# Audio.net
KiCad netlist of a schematic drawn in Altium Designer
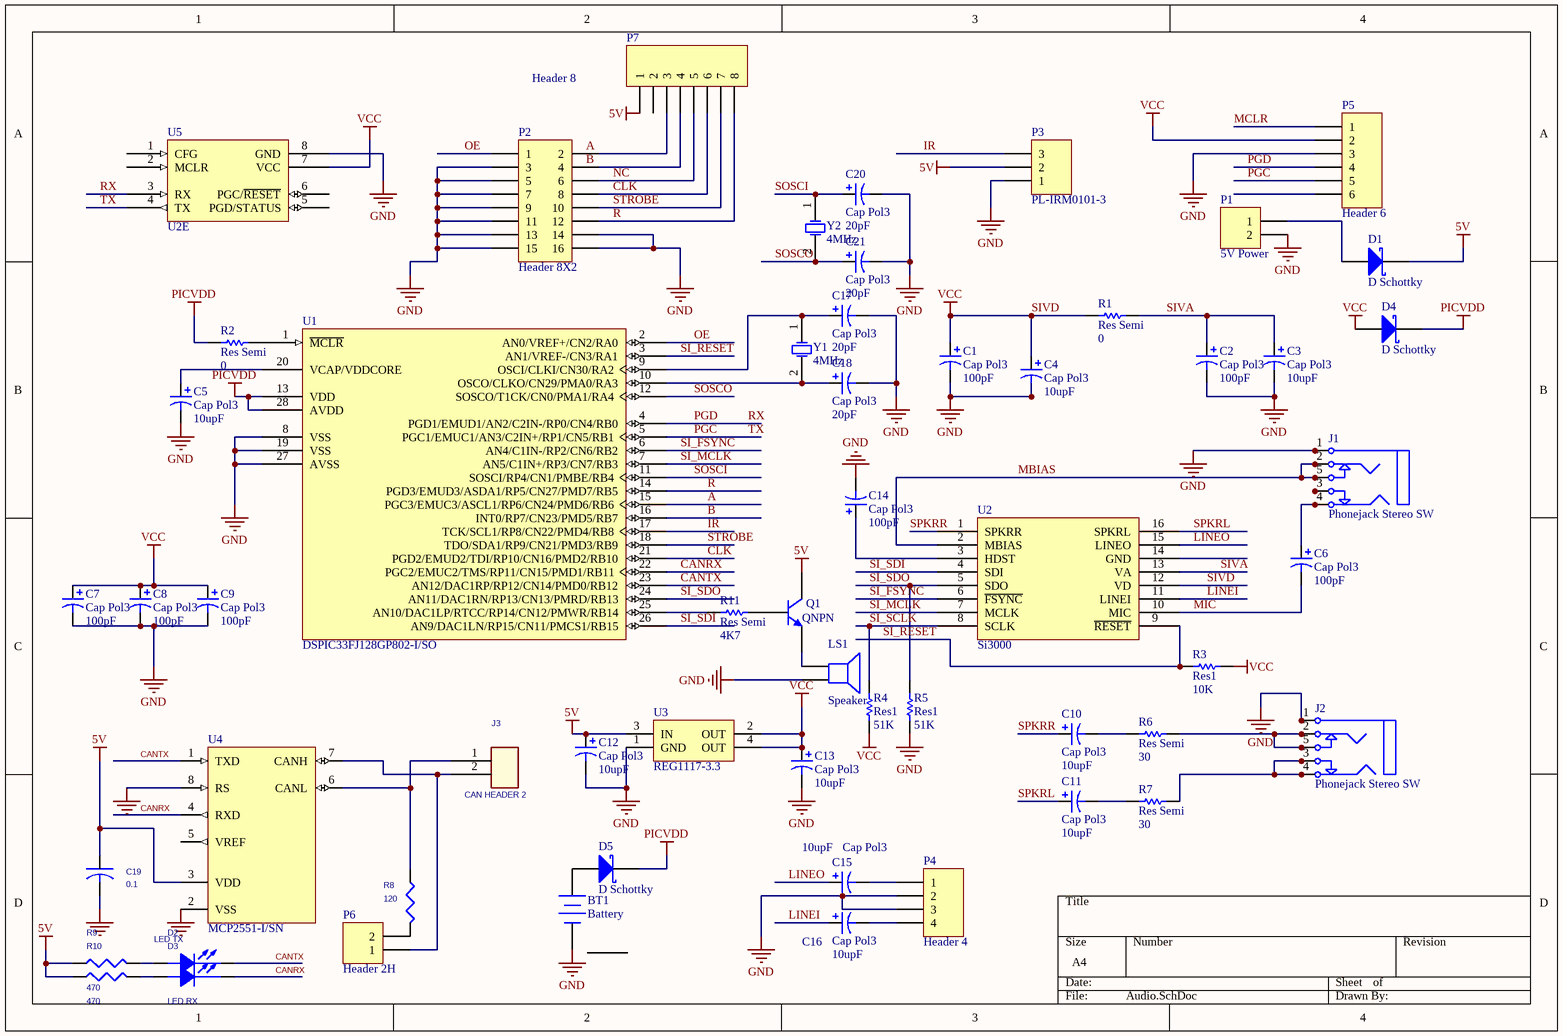
[diagram p0: Audio.SchDoc]

(export (version "E")
  (design (tool "Eeschema 10.0.6"))
  (components
    (comp (ref "BT1")
      (value "Battery")
      (footprint "CR2032")
      (description "Multicell Battery")
      (fields (field (name "PUBLISHER") "Altium Limited"))
      (libsource (lib "Miscellaneous Devices") (part "Battery"))
    )
    (comp (ref "C1")
      (value "Cap Pol3")
      (footprint "CAPC2012L")
      (description "Polarized Capacitor (Surface Mount)")
      (fields (field (name "ALTIUM_VALUE") "100pF") (field (name "PUBLISHER") "Altium Limited"))
      (libsource (lib "Miscellaneous Devices") (part "Cap Pol3"))
    )
    (comp (ref "C2")
      (value "Cap Pol3")
      (footprint "CAPC3225M")
      (description "Polarized Capacitor (Surface Mount)")
      (fields (field (name "ALTIUM_VALUE") "100pF") (field (name "PUBLISHER") "Altium Limited"))
      (libsource (lib "Miscellaneous Devices") (part "Cap Pol3"))
    )
    (comp (ref "C3")
      (value "Cap Pol3")
      (footprint "CAPC2012L")
      (description "Polarized Capacitor (Surface Mount)")
      (fields (field (name "ALTIUM_VALUE") "10upF") (field (name "PUBLISHER") "Altium Limited"))
      (libsource (lib "Miscellaneous Devices") (part "Cap Pol3"))
    )
    (comp (ref "C4")
      (value "Cap Pol3")
      (footprint "CAPC3225M")
      (description "Polarized Capacitor (Surface Mount)")
      (fields (field (name "ALTIUM_VALUE") "10upF") (field (name "PUBLISHER") "Altium Limited"))
      (libsource (lib "Miscellaneous Devices") (part "Cap Pol3"))
    )
    (comp (ref "C5")
      (value "Cap Pol3")
      (footprint "CAPC3225M")
      (description "Polarized Capacitor (Surface Mount)")
      (fields (field (name "ALTIUM_VALUE") "10upF") (field (name "PUBLISHER") "Altium Limited"))
      (libsource (lib "Miscellaneous Devices") (part "Cap Pol3"))
    )
    (comp (ref "C6")
      (value "Cap Pol3")
      (footprint "CAPC2012L")
      (description "Polarized Capacitor (Surface Mount)")
      (fields (field (name "ALTIUM_VALUE") "100pF") (field (name "PUBLISHER") "Altium Limited"))
      (libsource (lib "Miscellaneous Devices") (part "Cap Pol3"))
    )
    (comp (ref "C7")
      (value "Cap Pol3")
      (footprint "CAPC2012L")
      (description "Polarized Capacitor (Surface Mount)")
      (fields (field (name "ALTIUM_VALUE") "100pF") (field (name "PUBLISHER") "Altium Limited"))
      (libsource (lib "Miscellaneous Devices") (part "Cap Pol3"))
    )
    (comp (ref "C8")
      (value "Cap Pol3")
      (footprint "CAPC2012L")
      (description "Polarized Capacitor (Surface Mount)")
      (fields (field (name "ALTIUM_VALUE") "100pF") (field (name "PUBLISHER") "Altium Limited"))
      (libsource (lib "Miscellaneous Devices") (part "Cap Pol3"))
    )
    (comp (ref "C9")
      (value "Cap Pol3")
      (footprint "CAPC2012L")
      (description "Polarized Capacitor (Surface Mount)")
      (fields (field (name "ALTIUM_VALUE") "100pF") (field (name "PUBLISHER") "Altium Limited"))
      (libsource (lib "Miscellaneous Devices") (part "Cap Pol3"))
    )
    (comp (ref "C10")
      (value "Cap Pol3")
      (footprint "CAPC3225M")
      (description "Polarized Capacitor (Surface Mount)")
      (fields (field (name "ALTIUM_VALUE") "10upF") (field (name "PUBLISHER") "Altium Limited"))
      (libsource (lib "Miscellaneous Devices") (part "Cap Pol3"))
    )
    (comp (ref "C11")
      (value "Cap Pol3")
      (footprint "CAPC3225M")
      (description "Polarized Capacitor (Surface Mount)")
      (fields (field (name "ALTIUM_VALUE") "10upF") (field (name "PUBLISHER") "Altium Limited"))
      (libsource (lib "Miscellaneous Devices") (part "Cap Pol3"))
    )
    (comp (ref "C12")
      (value "Cap Pol3")
      (footprint "CAPC3225M")
      (description "Polarized Capacitor (Surface Mount)")
      (fields (field (name "ALTIUM_VALUE") "10upF") (field (name "PUBLISHER") "Altium Limited"))
      (libsource (lib "Miscellaneous Devices") (part "Cap Pol3"))
    )
    (comp (ref "C13")
      (value "Cap Pol3")
      (footprint "CAPC3225M")
      (description "Polarized Capacitor (Surface Mount)")
      (fields (field (name "ALTIUM_VALUE") "10upF") (field (name "PUBLISHER") "Altium Limited"))
      (libsource (lib "Miscellaneous Devices") (part "Cap Pol3"))
    )
    (comp (ref "C14")
      (value "Cap Pol3")
      (footprint "CAPC2012L")
      (description "Polarized Capacitor (Surface Mount)")
      (fields (field (name "ALTIUM_VALUE") "100pF") (field (name "PUBLISHER") "Altium Limited"))
      (libsource (lib "Miscellaneous Devices") (part "Cap Pol3"))
    )
    (comp (ref "C15")
      (value "Cap Pol3")
      (footprint "CAPC3225M")
      (description "Polarized Capacitor (Surface Mount)")
      (fields (field (name "ALTIUM_VALUE") "10upF") (field (name "PUBLISHER") "Altium Limited"))
      (libsource (lib "Miscellaneous Devices") (part "Cap Pol3"))
    )
    (comp (ref "C16")
      (value "Cap Pol3")
      (footprint "CAPC3225M")
      (description "Polarized Capacitor (Surface Mount)")
      (fields (field (name "ALTIUM_VALUE") "10upF") (field (name "PUBLISHER") "Altium Limited"))
      (libsource (lib "Miscellaneous Devices") (part "Cap Pol3"))
    )
    (comp (ref "C17")
      (value "Cap Pol3")
      (footprint "CAPC2012L")
      (description "Polarized Capacitor (Surface Mount)")
      (fields (field (name "ALTIUM_VALUE") "20pF") (field (name "PUBLISHER") "Altium Limited"))
      (libsource (lib "Miscellaneous Devices") (part "Cap Pol3"))
    )
    (comp (ref "C18")
      (value "Cap Pol3")
      (footprint "CAPC2012L")
      (description "Polarized Capacitor (Surface Mount)")
      (fields (field (name "ALTIUM_VALUE") "20pF") (field (name "PUBLISHER") "Altium Limited"))
      (libsource (lib "Miscellaneous Devices") (part "Cap Pol3"))
    )
    (comp (ref "C19") (value "0.1") (footprint "CAPC2012L") (libsource (lib "*") (part "C_Dup1")))
    (comp (ref "C20")
      (value "Cap Pol3")
      (footprint "CAPC2012L")
      (description "Polarized Capacitor (Surface Mount)")
      (fields (field (name "ALTIUM_VALUE") "20pF") (field (name "PUBLISHER") "Altium Limited"))
      (libsource (lib "Miscellaneous Devices") (part "Cap Pol3"))
    )
    (comp (ref "C21")
      (value "Cap Pol3")
      (footprint "CAPC2012L")
      (description "Polarized Capacitor (Surface Mount)")
      (fields (field (name "ALTIUM_VALUE") "20pF") (field (name "PUBLISHER") "Altium Limited"))
      (libsource (lib "Miscellaneous Devices") (part "Cap Pol3"))
    )
    (comp (ref "D1")
      (value "D Schottky")
      (footprint "DIO10.46-5.3x2.8")
      (description "Schottky Diode")
      (fields (field (name "PUBLISHER") "Altium Limited"))
      (libsource (lib "Miscellaneous Devices") (part "D Schottky"))
    )
    (comp (ref "D2") (value "LED TX") (footprint "DSO-F2/D6.1") (libsource (lib "*") (part "LED")))
    (comp (ref "D3") (value "LED RX") (footprint "DSO-F2/D6.1") (libsource (lib "*") (part "LED")))
    (comp (ref "D4")
      (value "D Schottky")
      (footprint "DIO10.46-5.3x2.8")
      (description "Schottky Diode")
      (fields (field (name "PUBLISHER") "Altium Limited"))
      (libsource (lib "Miscellaneous Devices") (part "D Schottky"))
    )
    (comp (ref "D5")
      (value "D Schottky")
      (footprint "DIO10.46-5.3x2.8")
      (description "Schottky Diode")
      (fields (field (name "PUBLISHER") "Altium Limited"))
      (libsource (lib "Miscellaneous Devices") (part "D Schottky"))
    )
    (comp (ref "J1")
      (value "Phonejack Stereo SW")
      (footprint "AUDIO-JACK")
      (description "3-Conductor Jack with 2 break contacts (normals) and 2 auxiliary make contacts")
      (fields (field (name "PUBLISHER") "Altium Limited"))
      (libsource (lib "Miscellaneous Connectors") (part "Phonejack Stereo SW"))
    )
    (comp (ref "J2")
      (value "Phonejack Stereo SW")
      (footprint "AUDIO-JACK")
      (description "3-Conductor Jack with 2 break contacts (normals) and 2 auxiliary make contacts")
      (fields (field (name "PUBLISHER") "Altium Limited"))
      (libsource (lib "Miscellaneous Connectors") (part "Phonejack Stereo SW"))
    )
    (comp (ref "J3")
      (value "CAN HEADER 2")
      (footprint "DOMINO SMALL 2 PIN_REV2")
      (libsource (lib "*") (part "CON2"))
    )
    (comp (ref "LS1")
      (value "Speaker")
      (footprint "PIN2")
      (description "Loudspeaker")
      (fields (field (name "PUBLISHER") "Altium Limited"))
      (libsource (lib "Miscellaneous Devices") (part "Speaker"))
    )
    (comp (ref "P1")
      (value "5V Power")
      (footprint "DOMINO SMALL 2 PIN_REV2")
      (description "Header, 2-Pin")
      (fields (field (name "PUBLISHER") "Altium Limited"))
      (libsource (lib "Miscellaneous Connectors") (part "Header 2"))
    )
    (comp (ref "P2")
      (value "Header 8X2")
      (footprint "HDR2X8")
      (description "Header, 8-Pin, Dual row")
      (fields (field (name "PUBLISHER") "Altium Limited"))
      (libsource (lib "Miscellaneous Connectors") (part "Header 8X2"))
    )
    (comp (ref "P3")
      (value "PL-IRM0101-3")
      (footprint "HDR1X3")
      (description "Header, 3-Pin")
      (fields (field (name "PUBLISHER") "Altium Limited"))
      (libsource (lib "Miscellaneous Connectors") (part "Header 3"))
    )
    (comp (ref "P4")
      (value "Header 4")
      (footprint "HDR1X4")
      (description "Header, 4-Pin")
      (fields (field (name "PUBLISHER") "Altium Limited"))
      (libsource (lib "Miscellaneous Connectors") (part "Header 4"))
    )
    (comp (ref "P5")
      (value "Header 6")
      (footprint "HDR1X6")
      (description "Header, 6-Pin")
      (fields (field (name "PUBLISHER") "Altium Limited"))
      (libsource (lib "Miscellaneous Connectors") (part "Header 6"))
    )
    (comp (ref "P6")
      (value "Header 2H")
      (footprint "RESC2012M")
      (description "Header, 2-Pin, Right Angle")
      (fields (field (name "PUBLISHER") "Altium Limited"))
      (libsource (lib "Miscellaneous Connectors") (part "Header 2H"))
    )
    (comp (ref "P7")
      (value "Header 8")
      (footprint "HDR1X8")
      (description "Header, 8-Pin")
      (fields (field (name "PUBLISHER") "Altium Limited"))
      (libsource (lib "Miscellaneous Connectors") (part "Header 8"))
    )
    (comp (ref "Q1")
      (value "QNPN")
      (footprint "SOT95P240-3M")
      (description "NPN Bipolar Transistor")
      (fields (field (name "PUBLISHER") "Altium Limited"))
      (libsource (lib "Miscellaneous Devices") (part "QNPN"))
    )
    (comp (ref "R1")
      (value "Res Semi")
      (footprint "RESC2012L")
      (description "Semiconductor Resistor")
      (fields (field (name "ALTIUM_VALUE") "0") (field (name "PUBLISHER") "Altium Limited"))
      (libsource (lib "Miscellaneous Devices") (part "Res Semi"))
    )
    (comp (ref "R2")
      (value "Res Semi")
      (footprint "RESC2012L")
      (description "Semiconductor Resistor")
      (fields (field (name "ALTIUM_VALUE") "0") (field (name "PUBLISHER") "Altium Limited"))
      (libsource (lib "Miscellaneous Devices") (part "Res Semi"))
    )
    (comp (ref "R3")
      (value "Res1")
      (footprint "RESC2012M")
      (description "Resistor")
      (fields (field (name "ALTIUM_VALUE") "10K") (field (name "PUBLISHER") "Altium Limited"))
      (libsource (lib "Miscellaneous Devices") (part "Res1"))
    )
    (comp (ref "R4")
      (value "Res1")
      (footprint "RESC2012M")
      (description "Resistor")
      (fields (field (name "ALTIUM_VALUE") "51K") (field (name "PUBLISHER") "Altium Limited"))
      (libsource (lib "Miscellaneous Devices") (part "Res1"))
    )
    (comp (ref "R5")
      (value "Res1")
      (footprint "RESC2012M")
      (description "Resistor")
      (fields (field (name "ALTIUM_VALUE") "51K") (field (name "PUBLISHER") "Altium Limited"))
      (libsource (lib "Miscellaneous Devices") (part "Res1"))
    )
    (comp (ref "R6")
      (value "Res Semi")
      (footprint "RESC2012L")
      (description "Semiconductor Resistor")
      (fields (field (name "ALTIUM_VALUE") "30") (field (name "PUBLISHER") "Altium Limited"))
      (libsource (lib "Miscellaneous Devices") (part "Res Semi"))
    )
    (comp (ref "R7")
      (value "Res Semi")
      (footprint "RESC2012L")
      (description "Semiconductor Resistor")
      (fields (field (name "ALTIUM_VALUE") "30") (field (name "PUBLISHER") "Altium Limited"))
      (libsource (lib "Miscellaneous Devices") (part "Res Semi"))
    )
    (comp (ref "R8") (value "120") (footprint "RESC2012M") (libsource (lib "*") (part "R_Dup1")))
    (comp (ref "R9") (value "470") (footprint "RESC2012M") (libsource (lib "*") (part "R_Dup1")))
    (comp (ref "R10") (value "470") (footprint "RESC2012M") (libsource (lib "*") (part "R_Dup1")))
    (comp (ref "R11")
      (value "Res Semi")
      (footprint "RESC2012L")
      (description "Semiconductor Resistor")
      (fields (field (name "ALTIUM_VALUE") "4K7") (field (name "PUBLISHER") "Altium Limited"))
      (libsource (lib "Miscellaneous Devices") (part "Res Semi"))
    )
    (comp (ref "U1")
      (value "DSPIC33FJ128GP802-I/SO")
      (footprint "SOIC-SO28_N")
      (fields (field (name "PUBLISHER") "Altium Limited"))
      (libsource (lib "Microchip DSC 16-Bit dsPIC33F") (part "DSPIC33FJ128GP802-I/SO"))
    )
    (comp (ref "U2")
      (value "Si3000")
      (footprint "SOIC127P1041-16M")
      (libsource (lib "AudioLib") (part "Si3000"))
    )
    (comp (ref "U3")
      (value "REG1117-3.3")
      (footprint "ZZ311")
      (description "800mA and 1A Low Dropout Positive Regulator 2.85V, 3.3V, 5V, and Adjustable")
      (fields (field (name "PUBLISHER") "Altium Limited"))
      (libsource (lib "BB Power Mgt Voltage Regulator") (part "REG1117-3.3"))
    )
    (comp (ref "U4")
      (value "MCP2551-I/SN")
      (footprint "SOIC-SN8_N")
      (description "High-Speed CAN Transceiver, 8-Pin SOIC, Industrial Temperature")
      (fields (field (name "PUBLISHER") "Altium Limited"))
      (libsource (lib "Microchip Interface") (part "MCP2551-I/SN"))
    )
    (comp (ref "U5") (value "U2E") (footprint "U2E") (libsource (lib "CUTL") (part "U2E")))
    (comp (ref "Y1")
      (value "4MHz")
      (footprint "BCY-W2/E4.7")
      (description "Crystal Oscillator")
      (fields (field (name "PUBLISHER") "Altium Limited"))
      (libsource (lib "Miscellaneous Devices") (part "XTAL"))
    )
    (comp (ref "Y2")
      (value "4MHz")
      (footprint "BCY-W2/D2.1")
      (description "Crystal Oscillator")
      (fields (field (name "PUBLISHER") "Altium Limited"))
      (libsource (lib "Miscellaneous Devices") (part "XTAL"))
    )
  )
  (nets
    (net (code "1") (name "/A") (class "Default")
      (node (ref "U1") (pin "15") (pinfunction "PGC3/EMUC3/ASCL1/RP6/CN24/PMD6/RB6_15") (pintype "bidirectional"))
    )
    (net (code "2") (name "/B") (class "Default")
      (node (ref "U1") (pin "16") (pinfunction "INT0/RP7/CN23/PMD5/RB7_16") (pintype "bidirectional"))
    )
    (net (code "3") (name "/CANRX") (class "Default")
      (node (ref "D3") (pin "2") (pinfunction "CATHODE_2") (pintype "passive"))
      (node (ref "U1") (pin "22") (pinfunction "PGC2/EMUC2/TMS/RP11/CN15/PMD1/RB11_22") (pintype "bidirectional"))
      (node (ref "U4") (pin "4") (pinfunction "RXD_4") (pintype "output"))
    )
    (net (code "4") (name "/CANTX") (class "Default")
      (node (ref "D2") (pin "2") (pinfunction "CATHODE_2") (pintype "passive"))
      (node (ref "U1") (pin "23") (pinfunction "AN12/DAC1RP/RP12/CN14/PMD0/RB12_23") (pintype "bidirectional"))
      (node (ref "U4") (pin "1") (pinfunction "TXD_1") (pintype "input"))
    )
    (net (code "5") (name "/CLK") (class "Default")
      (node (ref "P2") (pin "8") (pinfunction "8_8") (pintype "passive"))
      (node (ref "P7") (pin "6") (pinfunction "6_6") (pintype "passive"))
      (node (ref "U1") (pin "21") (pinfunction "PGD2/EMUD2/TDI/RP10/CN16/PMD2/RB10_21") (pintype "bidirectional"))
    )
    (net (code "6") (name "/IR") (class "Default")
      (node (ref "P3") (pin "3") (pinfunction "3_3") (pintype "passive"))
      (node (ref "U1") (pin "17") (pinfunction "TCK/SCL1/RP8/CN22/PMD4/RB8_17") (pintype "bidirectional"))
    )
    (net (code "7") (name "/LINEI") (class "Default")
      (node (ref "C16") (pin "1") (pinfunction "1_1") (pintype "passive"))
      (node (ref "U2") (pin "11") (pinfunction "LINEI_11") (pintype "passive"))
    )
    (net (code "8") (name "/LINEO") (class "Default")
      (node (ref "C15") (pin "1") (pinfunction "1_1") (pintype "passive"))
      (node (ref "U2") (pin "15") (pinfunction "LINEO_15") (pintype "passive"))
    )
    (net (code "9") (name "/MBIAS") (class "Default")
      (node (ref "J1") (pin "2") (pinfunction "2_2") (pintype "passive"))
      (node (ref "J1") (pin "2A") (pinfunction "2A_2A") (pintype "passive"))
      (node (ref "J1") (pin "2B") (pinfunction "2B_2B") (pintype "passive"))
      (node (ref "J1") (pin "5") (pinfunction "5_5") (pintype "passive"))
      (node (ref "J1") (pin "5A") (pinfunction "5A_5A") (pintype "passive"))
      (node (ref "J1") (pin "5B") (pinfunction "5B_5B") (pintype "passive"))
      (node (ref "U2") (pin "2") (pinfunction "MBIAS_2") (pintype "passive"))
    )
    (net (code "10") (name "/MCLR") (class "Default")
      (node (ref "P5") (pin "1") (pinfunction "1_1") (pintype "passive"))
    )
    (net (code "11") (name "/MIC") (class "Default")
      (node (ref "C6") (pin "2") (pinfunction "2_2") (pintype "passive"))
      (node (ref "U2") (pin "10") (pinfunction "MIC_10") (pintype "passive"))
    )
    (net (code "12") (name "/NC") (class "Default")
      (node (ref "P2") (pin "6") (pinfunction "6_6") (pintype "passive"))
      (node (ref "P7") (pin "5") (pinfunction "5_5") (pintype "passive"))
    )
    (net (code "13") (name "/OE") (class "Default")
      (node (ref "P2") (pin "1") (pinfunction "1_1") (pintype "passive"))
      (node (ref "U1") (pin "2") (pinfunction "AN0/VREF+/CN2/RA0_2") (pintype "bidirectional"))
    )
    (net (code "14") (name "/PGC") (class "Default")
      (node (ref "P5") (pin "5") (pinfunction "5_5") (pintype "passive"))
      (node (ref "U1") (pin "5") (pinfunction "PGC1/EMUC1/AN3/C2IN+/RP1/CN5/RB1_5") (pintype "bidirectional"))
      (node (ref "U5") (pin "4") (pinfunction "TX_4") (pintype "output"))
    )
    (net (code "15") (name "/PGD") (class "Default")
      (node (ref "P5") (pin "4") (pinfunction "4_4") (pintype "passive"))
      (node (ref "U1") (pin "4") (pinfunction "PGD1/EMUD1/AN2/C2IN-/RP0/CN4/RB0_4") (pintype "bidirectional"))
      (node (ref "U5") (pin "3") (pinfunction "RX_3") (pintype "input"))
    )
    (net (code "16") (name "/R") (class "Default")
      (node (ref "P2") (pin "12") (pinfunction "12_12") (pintype "passive"))
      (node (ref "P7") (pin "8") (pinfunction "8_8") (pintype "passive"))
      (node (ref "U1") (pin "14") (pinfunction "PGD3/EMUD3/ASDA1/RP5/CN27/PMD7/RB5_14") (pintype "bidirectional"))
    )
    (net (code "17") (name "/SIVA") (class "Default")
      (node (ref "C2") (pin "1") (pinfunction "1_1") (pintype "passive"))
      (node (ref "C3") (pin "1") (pinfunction "1_1") (pintype "passive"))
      (node (ref "R1") (pin "2") (pinfunction "2_2") (pintype "passive"))
      (node (ref "U2") (pin "13") (pinfunction "VA_13") (pintype "passive"))
    )
    (net (code "18") (name "/SI_FSYNC") (class "Default")
      (node (ref "U1") (pin "6") (pinfunction "AN4/C1IN-/RP2/CN6/RB2_6") (pintype "bidirectional"))
      (node (ref "U2") (pin "6") (pinfunction "~{FSYNC}_6") (pintype "passive"))
    )
    (net (code "19") (name "/SI_MCLK") (class "Default")
      (node (ref "U1") (pin "7") (pinfunction "AN5/C1IN+/RP3/CN7/RB3_7") (pintype "bidirectional"))
      (node (ref "U2") (pin "7") (pinfunction "MCLK_7") (pintype "passive"))
    )
    (net (code "20") (name "/SI_RESET") (class "Default")
      (node (ref "R3") (pin "2") (pinfunction "2_2") (pintype "passive"))
      (node (ref "U1") (pin "3") (pinfunction "AN1/VREF-/CN3/RA1_3") (pintype "bidirectional"))
      (node (ref "U2") (pin "9") (pinfunction "~{RESET}_9") (pintype "passive"))
    )
    (net (code "21") (name "/SI_SCLK") (class "Default")
      (node (ref "R4") (pin "2") (pinfunction "2_2") (pintype "passive"))
      (node (ref "U2") (pin "8") (pinfunction "SCLK_8") (pintype "passive"))
    )
    (net (code "22") (name "/SI_SDI") (class "Default")
      (node (ref "U1") (pin "26") (pinfunction "AN9/DAC1LN/RP15/CN11/PMCS1/RB15_26") (pintype "bidirectional"))
      (node (ref "U2") (pin "4") (pinfunction "SDI_4") (pintype "passive"))
    )
    (net (code "23") (name "/SI_SDO") (class "Default")
      (node (ref "R5") (pin "2") (pinfunction "2_2") (pintype "passive"))
      (node (ref "U1") (pin "24") (pinfunction "AN11/DAC1RN/RP13/CN13/PMRD/RB13_24") (pintype "bidirectional"))
      (node (ref "U2") (pin "5") (pinfunction "SDO_5") (pintype "passive"))
    )
    (net (code "24") (name "/SOSCI") (class "Default")
      (node (ref "C20") (pin "1") (pinfunction "1_1") (pintype "passive"))
      (node (ref "U1") (pin "11") (pinfunction "SOSCI/RP4/CN1/PMBE/RB4_11") (pintype "bidirectional"))
      (node (ref "Y2") (pin "1") (pinfunction "OSC1_1") (pintype "passive"))
    )
    (net (code "25") (name "/SOSCO") (class "Default")
      (node (ref "C21") (pin "1") (pinfunction "1_1") (pintype "passive"))
      (node (ref "U1") (pin "12") (pinfunction "SOSCO/T1CK/CN0/PMA1/RA4_12") (pintype "bidirectional"))
      (node (ref "Y2") (pin "2") (pinfunction "OSC2_2") (pintype "passive"))
    )
    (net (code "26") (name "/SPKRL") (class "Default")
      (node (ref "C11") (pin "1") (pinfunction "1_1") (pintype "passive"))
      (node (ref "U2") (pin "16") (pinfunction "SPKRL_16") (pintype "passive"))
    )
    (net (code "27") (name "/SPKRR") (class "Default")
      (node (ref "C10") (pin "1") (pinfunction "1_1") (pintype "passive"))
      (node (ref "U2") (pin "1") (pinfunction "SPKRR_1") (pintype "passive"))
    )
    (net (code "28") (name "/STROBE") (class "Default")
      (node (ref "P2") (pin "10") (pinfunction "10_10") (pintype "passive"))
      (node (ref "P7") (pin "7") (pinfunction "7_7") (pintype "passive"))
      (node (ref "U1") (pin "18") (pinfunction "TDO/SDA1/RP9/CN21/PMD3/RB9_18") (pintype "bidirectional"))
    )
    (net (code "29") (name "5V") (class "Default")
      (node (ref "C12") (pin "1") (pinfunction "1_1") (pintype "passive"))
      (node (ref "C19") (pin "1") (pinfunction "1_1") (pintype "passive"))
      (node (ref "D1") (pin "2") (pinfunction "K_2") (pintype "passive"))
      (node (ref "P3") (pin "2") (pinfunction "2_2") (pintype "passive"))
      (node (ref "P7") (pin "1") (pinfunction "1_1") (pintype "passive"))
      (node (ref "Q1") (pin "3") (pinfunction "C_3") (pintype "passive"))
      (node (ref "R10") (pin "1") (pinfunction "1_1") (pintype "passive"))
      (node (ref "R9") (pin "1") (pinfunction "1_1") (pintype "passive"))
      (node (ref "U3") (pin "3") (pinfunction "IN_3") (pintype "power_in"))
      (node (ref "U4") (pin "3") (pinfunction "VDD_3") (pintype "power_in"))
    )
    (net (code "30") (name "GND") (class "Default")
      (node (ref "BT1") (pin "1") (pinfunction "-_1") (pintype "passive"))
      (node (ref "C1") (pin "2") (pinfunction "2_2") (pintype "passive"))
      (node (ref "C12") (pin "2") (pinfunction "2_2") (pintype "passive"))
      (node (ref "C13") (pin "2") (pinfunction "2_2") (pintype "passive"))
      (node (ref "C14") (pin "2") (pinfunction "2_2") (pintype "passive"))
      (node (ref "C17") (pin "2") (pinfunction "2_2") (pintype "passive"))
      (node (ref "C18") (pin "2") (pinfunction "2_2") (pintype "passive"))
      (node (ref "C19") (pin "2") (pinfunction "2_2") (pintype "passive"))
      (node (ref "C2") (pin "2") (pinfunction "2_2") (pintype "passive"))
      (node (ref "C20") (pin "2") (pinfunction "2_2") (pintype "passive"))
      (node (ref "C21") (pin "2") (pinfunction "2_2") (pintype "passive"))
      (node (ref "C3") (pin "2") (pinfunction "2_2") (pintype "passive"))
      (node (ref "C4") (pin "2") (pinfunction "2_2") (pintype "passive"))
      (node (ref "C5") (pin "2") (pinfunction "2_2") (pintype "passive"))
      (node (ref "C7") (pin "2") (pinfunction "2_2") (pintype "passive"))
      (node (ref "C8") (pin "2") (pinfunction "2_2") (pintype "passive"))
      (node (ref "C9") (pin "2") (pinfunction "2_2") (pintype "passive"))
      (node (ref "J1") (pin "1") (pinfunction "1_1") (pintype "passive"))
      (node (ref "J1") (pin "1A") (pinfunction "1A_1A") (pintype "passive"))
      (node (ref "J1") (pin "1B") (pinfunction "1B_1B") (pintype "passive"))
      (node (ref "J2") (pin "1") (pinfunction "1_1") (pintype "passive"))
      (node (ref "J2") (pin "1A") (pinfunction "1A_1A") (pintype "passive"))
      (node (ref "J2") (pin "1B") (pinfunction "1B_1B") (pintype "passive"))
      (node (ref "LS1") (pin "2") (pinfunction "2_2") (pintype "passive"))
      (node (ref "P1") (pin "2") (pinfunction "2_2") (pintype "passive"))
      (node (ref "P2") (pin "11") (pinfunction "11_11") (pintype "passive"))
      (node (ref "P2") (pin "13") (pinfunction "13_13") (pintype "passive"))
      (node (ref "P2") (pin "14") (pinfunction "14_14") (pintype "passive"))
      (node (ref "P2") (pin "15") (pinfunction "15_15") (pintype "passive"))
      (node (ref "P2") (pin "16") (pinfunction "16_16") (pintype "passive"))
      (node (ref "P2") (pin "3") (pinfunction "3_3") (pintype "passive"))
      (node (ref "P2") (pin "5") (pinfunction "5_5") (pintype "passive"))
      (node (ref "P2") (pin "7") (pinfunction "7_7") (pintype "passive"))
      (node (ref "P2") (pin "9") (pinfunction "9_9") (pintype "passive"))
      (node (ref "P3") (pin "1") (pinfunction "1_1") (pintype "passive"))
      (node (ref "P4") (pin "2") (pinfunction "2_2") (pintype "passive"))
      (node (ref "P4") (pin "3") (pinfunction "3_3") (pintype "passive"))
      (node (ref "P5") (pin "3") (pinfunction "3_3") (pintype "passive"))
      (node (ref "R5") (pin "1") (pinfunction "1_1") (pintype "passive"))
      (node (ref "U1") (pin "19") (pinfunction "VSS_19") (pintype "power_in"))
      (node (ref "U1") (pin "27") (pinfunction "AVSS_27") (pintype "power_in"))
      (node (ref "U1") (pin "8") (pinfunction "VSS_8") (pintype "power_in"))
      (node (ref "U3") (pin "1") (pinfunction "GND_1") (pintype "power_in"))
      (node (ref "U4") (pin "2") (pinfunction "VSS_2") (pintype "power_in"))
      (node (ref "U4") (pin "8") (pinfunction "RS_8") (pintype "input"))
      (node (ref "U5") (pin "8") (pinfunction "GND_8") (pintype "power_in"))
    )
    (net (code "31") (name "Net-(C6-Pad1)") (class "Default")
      (node (ref "C6") (pin "1") (pinfunction "1_1") (pintype "passive"))
      (node (ref "J1") (pin "4") (pinfunction "4_4") (pintype "passive"))
      (node (ref "J1") (pin "4A") (pinfunction "4A_4A") (pintype "passive"))
      (node (ref "J1") (pin "4B") (pinfunction "4B_4B") (pintype "passive"))
    )
    (net (code "32") (name "Net-(C10-Pad2)") (class "Default")
      (node (ref "C10") (pin "2") (pinfunction "2_2") (pintype "passive"))
      (node (ref "R6") (pin "1") (pinfunction "1_1") (pintype "passive"))
    )
    (net (code "33") (name "Net-(C11-Pad2)") (class "Default")
      (node (ref "C11") (pin "2") (pinfunction "2_2") (pintype "passive"))
      (node (ref "R7") (pin "1") (pinfunction "1_1") (pintype "passive"))
    )
    (net (code "34") (name "Net-(C15-Pad2)") (class "Default")
      (node (ref "C15") (pin "2") (pinfunction "2_2") (pintype "passive"))
      (node (ref "P4") (pin "1") (pinfunction "1_1") (pintype "passive"))
    )
    (net (code "35") (name "Net-(C16-Pad2)") (class "Default")
      (node (ref "C16") (pin "2") (pinfunction "2_2") (pintype "passive"))
      (node (ref "P4") (pin "4") (pinfunction "4_4") (pintype "passive"))
    )
    (net (code "36") (name "Net-(D1-A)") (class "Default")
      (node (ref "D1") (pin "1") (pinfunction "A_1") (pintype "passive"))
      (node (ref "P1") (pin "1") (pinfunction "1_1") (pintype "passive"))
    )
    (net (code "37") (name "Net-(D2-ANODE)") (class "Default")
      (node (ref "D2") (pin "1") (pinfunction "ANODE_1") (pintype "passive"))
      (node (ref "R9") (pin "2") (pinfunction "2_2") (pintype "passive"))
    )
    (net (code "38") (name "Net-(D3-ANODE)") (class "Default")
      (node (ref "D3") (pin "1") (pinfunction "ANODE_1") (pintype "passive"))
      (node (ref "R10") (pin "2") (pinfunction "2_2") (pintype "passive"))
    )
    (net (code "39") (name "Net-(D5-A)") (class "Default")
      (node (ref "BT1") (pin "2") (pinfunction "+_2") (pintype "passive"))
      (node (ref "D5") (pin "1") (pinfunction "A_1") (pintype "passive"))
    )
    (net (code "40") (name "Net-(J1-Pad3)") (class "Default")
      (node (ref "J1") (pin "3") (pinfunction "3_3") (pintype "passive"))
      (node (ref "J1") (pin "3A") (pinfunction "3A_3A") (pintype "passive"))
      (node (ref "J1") (pin "3B") (pinfunction "3B_3B") (pintype "passive"))
    )
    (net (code "41") (name "Net-(J2-Pad2)") (class "Default")
      (node (ref "J2") (pin "2") (pinfunction "2_2") (pintype "passive"))
      (node (ref "J2") (pin "2A") (pinfunction "2A_2A") (pintype "passive"))
      (node (ref "J2") (pin "2B") (pinfunction "2B_2B") (pintype "passive"))
      (node (ref "J2") (pin "5") (pinfunction "5_5") (pintype "passive"))
      (node (ref "J2") (pin "5A") (pinfunction "5A_5A") (pintype "passive"))
      (node (ref "J2") (pin "5B") (pinfunction "5B_5B") (pintype "passive"))
      (node (ref "R6") (pin "2") (pinfunction "2_2") (pintype "passive"))
    )
    (net (code "42") (name "Net-(J2-Pad3)") (class "Default")
      (node (ref "J2") (pin "3") (pinfunction "3_3") (pintype "passive"))
      (node (ref "J2") (pin "3A") (pinfunction "3A_3A") (pintype "passive"))
      (node (ref "J2") (pin "3B") (pinfunction "3B_3B") (pintype "passive"))
      (node (ref "J2") (pin "4") (pinfunction "4_4") (pintype "passive"))
      (node (ref "J2") (pin "4A") (pinfunction "4A_4A") (pintype "passive"))
      (node (ref "J2") (pin "4B") (pinfunction "4B_4B") (pintype "passive"))
      (node (ref "R7") (pin "2") (pinfunction "2_2") (pintype "passive"))
    )
    (net (code "43") (name "Net-(P2-Pad2)") (class "Default")
      (node (ref "P2") (pin "2") (pinfunction "2_2") (pintype "passive"))
      (node (ref "P7") (pin "3") (pinfunction "3_3") (pintype "passive"))
    )
    (net (code "44") (name "Net-(P2-Pad4)") (class "Default")
      (node (ref "P2") (pin "4") (pinfunction "4_4") (pintype "passive"))
      (node (ref "P7") (pin "4") (pinfunction "4_4") (pintype "passive"))
    )
    (net (code "45") (name "Net-(P6-Pad2)") (class "Default")
      (node (ref "P6") (pin "2") (pinfunction "2_2") (pintype "passive"))
      (node (ref "R8") (pin "2") (pinfunction "2_2") (pintype "passive"))
    )
    (net (code "46") (name "Net-(Q1-B)") (class "Default")
      (node (ref "Q1") (pin "1") (pinfunction "B_1") (pintype "passive"))
      (node (ref "R11") (pin "2") (pinfunction "2_2") (pintype "passive"))
    )
    (net (code "47") (name "Net-(Q1-E)") (class "Default")
      (node (ref "LS1") (pin "1") (pinfunction "1_1") (pintype "passive"))
      (node (ref "Q1") (pin "2") (pinfunction "E_2") (pintype "passive"))
    )
    (net (code "48") (name "Net-(U1-AN10{slash}DAC1LP{slash}RTCC{slash}RP14{slash}CN12{slash}PMWR{slash}RB14)") (class "Default")
      (node (ref "R11") (pin "1") (pinfunction "1_1") (pintype "passive"))
      (node (ref "U1") (pin "25") (pinfunction "AN10/DAC1LP/RTCC/RP14/CN12/PMWR/RB14_25") (pintype "bidirectional"))
    )
    (net (code "49") (name "Net-(U1-OSCI{slash}CLKI{slash}CN30{slash}RA2)") (class "Default")
      (node (ref "C17") (pin "1") (pinfunction "1_1") (pintype "passive"))
      (node (ref "U1") (pin "9") (pinfunction "OSCI/CLKI/CN30/RA2_9") (pintype "bidirectional"))
      (node (ref "Y1") (pin "1") (pinfunction "OSC1_1") (pintype "passive"))
    )
    (net (code "50") (name "Net-(U1-OSCO{slash}CLKO{slash}CN29{slash}PMA0{slash}RA3)") (class "Default")
      (node (ref "C18") (pin "1") (pinfunction "1_1") (pintype "passive"))
      (node (ref "U1") (pin "10") (pinfunction "OSCO/CLKO/CN29/PMA0/RA3_10") (pintype "bidirectional"))
      (node (ref "Y1") (pin "2") (pinfunction "OSC2_2") (pintype "passive"))
    )
    (net (code "51") (name "Net-(U1-VCAP{slash}VDDCORE)") (class "Default")
      (node (ref "C5") (pin "1") (pinfunction "1_1") (pintype "passive"))
      (node (ref "U1") (pin "20") (pinfunction "VCAP/VDDCORE_20") (pintype "power_in"))
    )
    (net (code "52") (name "Net-(U1-~{MCLR})") (class "Default")
      (node (ref "R2") (pin "2") (pinfunction "2_2") (pintype "passive"))
      (node (ref "U1") (pin "1") (pinfunction "~{MCLR}_1") (pintype "input"))
    )
    (net (code "53") (name "Net-(U2-HDST)") (class "Default")
      (node (ref "C14") (pin "1") (pinfunction "1_1") (pintype "passive"))
      (node (ref "U2") (pin "3") (pinfunction "HDST_3") (pintype "passive"))
    )
    (net (code "54") (name "Net-(U4-CANH)") (class "Default")
      (node (ref "J3") (pin "2") (pinfunction "2_2") (pintype "passive"))
      (node (ref "P6") (pin "1") (pinfunction "1_1") (pintype "passive"))
      (node (ref "U4") (pin "7") (pinfunction "CANH_7") (pintype "bidirectional"))
    )
    (net (code "55") (name "Net-(U4-CANL)") (class "Default")
      (node (ref "J3") (pin "1") (pinfunction "1_1") (pintype "passive"))
      (node (ref "R8") (pin "1") (pinfunction "1_1") (pintype "passive"))
      (node (ref "U4") (pin "6") (pinfunction "CANL_6") (pintype "bidirectional"))
    )
    (net (code "56") (name "PICVDD") (class "Default")
      (node (ref "D4") (pin "2") (pinfunction "K_2") (pintype "passive"))
      (node (ref "D5") (pin "2") (pinfunction "K_2") (pintype "passive"))
      (node (ref "R2") (pin "1") (pinfunction "1_1") (pintype "passive"))
      (node (ref "U1") (pin "13") (pinfunction "VDD_13") (pintype "power_in"))
      (node (ref "U1") (pin "28") (pinfunction "AVDD_28") (pintype "power_in"))
    )
    (net (code "57") (name "VCC") (class "Default")
      (node (ref "C1") (pin "1") (pinfunction "1_1") (pintype "passive"))
      (node (ref "C13") (pin "1") (pinfunction "1_1") (pintype "passive"))
      (node (ref "C4") (pin "1") (pinfunction "1_1") (pintype "passive"))
      (node (ref "C7") (pin "1") (pinfunction "1_1") (pintype "passive"))
      (node (ref "C8") (pin "1") (pinfunction "1_1") (pintype "passive"))
      (node (ref "C9") (pin "1") (pinfunction "1_1") (pintype "passive"))
      (node (ref "D4") (pin "1") (pinfunction "A_1") (pintype "passive"))
      (node (ref "P5") (pin "2") (pinfunction "2_2") (pintype "passive"))
      (node (ref "R1") (pin "1") (pinfunction "1_1") (pintype "passive"))
      (node (ref "R3") (pin "1") (pinfunction "1_1") (pintype "passive"))
      (node (ref "R4") (pin "1") (pinfunction "1_1") (pintype "passive"))
      (node (ref "U2") (pin "12") (pinfunction "VD_12") (pintype "passive"))
      (node (ref "U3") (pin "2") (pinfunction "OUT_2") (pintype "power_in"))
      (node (ref "U3") (pin "4") (pinfunction "OUT_4") (pintype "power_in"))
      (node (ref "U5") (pin "7") (pinfunction "VCC_7") (pintype "power_in"))
    )
    (net (code "58") (name "unconnected-(BT1-+-Pad3)") (class "Default")
      (node (ref "BT1") (pin "3") (pinfunction "+_3") (pintype "passive"))
    )
    (net (code "59") (name "unconnected-(P5-Pad6)") (class "Default")
      (node (ref "P5") (pin "6") (pinfunction "6_6") (pintype "passive"))
    )
    (net (code "60") (name "unconnected-(P7-Pad2)") (class "Default")
      (node (ref "P7") (pin "2") (pinfunction "2_2") (pintype "passive"))
    )
    (net (code "61") (name "unconnected-(U2-GND-Pad14)") (class "Default")
      (node (ref "U2") (pin "14") (pinfunction "GND_14") (pintype "passive"))
    )
    (net (code "62") (name "unconnected-(U4-VREF-Pad5)") (class "Default")
      (node (ref "U4") (pin "5") (pinfunction "VREF_5") (pintype "output"))
    )
    (net (code "63") (name "unconnected-(U5-CFG-Pad1)") (class "Default")
      (node (ref "U5") (pin "1") (pinfunction "CFG_1") (pintype "input"))
    )
    (net (code "64") (name "unconnected-(U5-MCLR-Pad2)") (class "Default")
      (node (ref "U5") (pin "2") (pinfunction "MCLR_2") (pintype "input"))
    )
    (net (code "65") (name "unconnected-(U5-PGC{slash}~{RESET}-Pad6)") (class "Default")
      (node (ref "U5") (pin "6") (pinfunction "PGC/~{RESET}_6") (pintype "bidirectional"))
    )
    (net (code "66") (name "unconnected-(U5-PGD{slash}STATUS-Pad5)") (class "Default")
      (node (ref "U5") (pin "5") (pinfunction "PGD/STATUS_5") (pintype "bidirectional"))
    )
  )
)
